# emu.net
KiCad netlist of a schematic drawn in Altium Designer
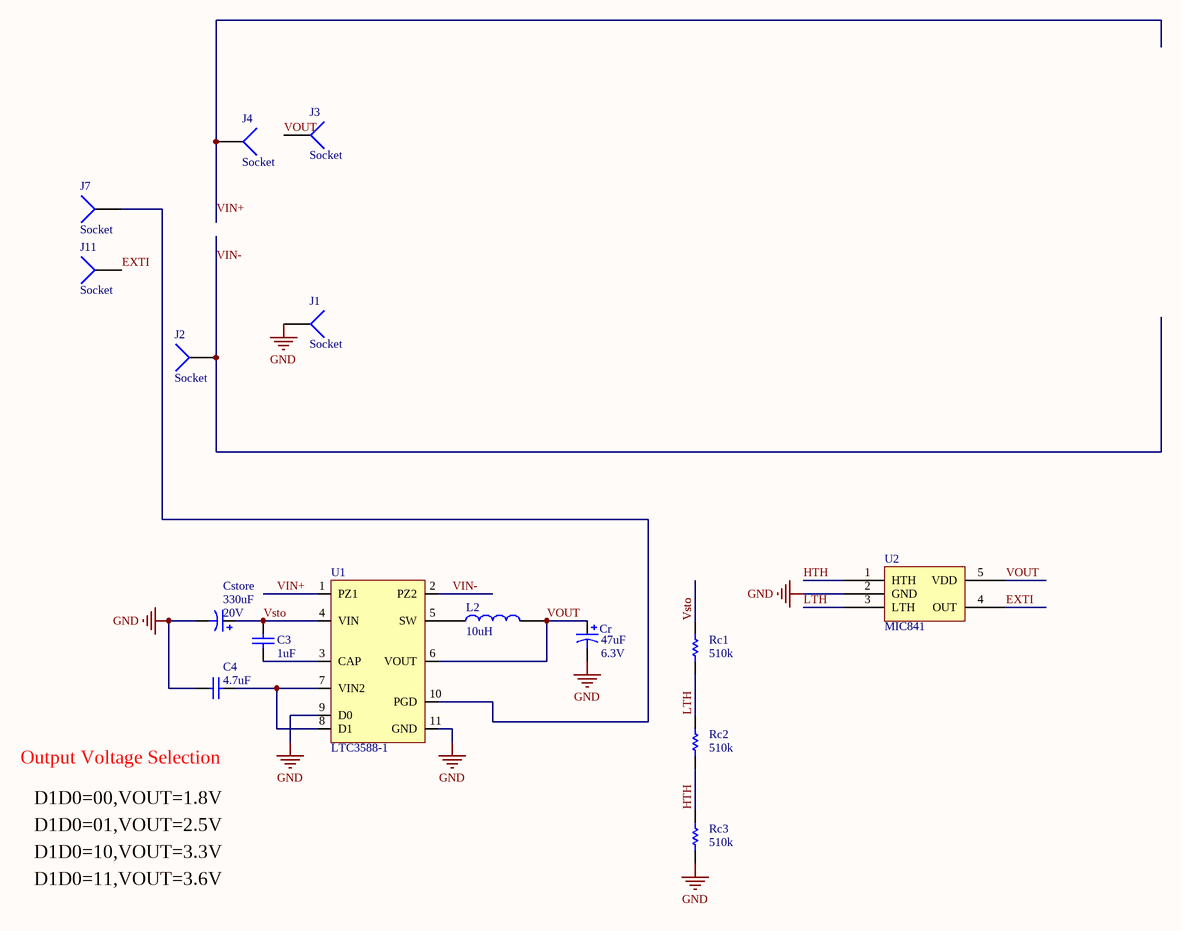
[diagram p0: emu.SchDoc]

(export (version "E")
  (design (tool "Eeschema 10.0.6"))
  (components
    (comp (ref "C3")
      (value "1uF")
      (footprint "6-0805_N")
      (description "Capacitor")
      (fields (field (name "Comment") "CAP") (field (name "PUBLISHER") "Altium Limited"))
      (libsource (lib "Harry_PCBLib") (part "Cap"))
    )
    (comp (ref "C4")
      (value "4.7uF")
      (footprint "6-0805_N")
      (description "Capacitor")
      (fields (field (name "Comment") "CAP") (field (name "PUBLISHER") "Altium Limited"))
      (libsource (lib "Harry_PCBLib") (part "Cap"))
    )
    (comp (ref "Cr")
      (value "6.3V")
      (footprint "3216[1206]")
      (description "Polarized Capacitor (Radial)")
      (fields (field (name "ALTIUM_VALUE") "47uF") (field (name "PUBLISHER") "Altium Limited"))
      (libsource (lib "Miscellaneous Devices") (part "Cap Pol1"))
    )
    (comp (ref "Cstore")
      (value "330uF")
      (footprint "HDR1X2")
      (description "Polarized Capacitor (Radial)")
      (fields
        (field (name "NOMINAL VOLTAGE") "20V")
        (field (name "Comment") "Cap Pol1")
        (field (name "PUBLISHER") "Altium Limited")
      )
      (libsource (lib "Miscellaneous Devices") (part "Cap Pol1"))
    )
    (comp (ref "J1")
      (value "Socket")
      (footprint "PIN1")
      (fields (field (name "PUBLISHER") "Altium Limited"))
      (libsource (lib "Miscellaneous Connectors") (part "Socket"))
    )
    (comp (ref "J2")
      (value "Socket")
      (footprint "PIN1")
      (fields (field (name "PUBLISHER") "Altium Limited"))
      (libsource (lib "Miscellaneous Connectors") (part "Socket"))
    )
    (comp (ref "J3")
      (value "Socket")
      (footprint "PIN1")
      (fields (field (name "PUBLISHER") "Altium Limited"))
      (libsource (lib "Miscellaneous Connectors") (part "Socket"))
    )
    (comp (ref "J4")
      (value "Socket")
      (footprint "PIN1")
      (fields (field (name "PUBLISHER") "Altium Limited"))
      (libsource (lib "Miscellaneous Connectors") (part "Socket"))
    )
    (comp (ref "J7")
      (value "Socket")
      (footprint "PIN1")
      (fields (field (name "PUBLISHER") "Altium Limited"))
      (libsource (lib "Miscellaneous Connectors") (part "Socket"))
    )
    (comp (ref "J11")
      (value "Socket")
      (footprint "PIN1")
      (fields (field (name "PUBLISHER") "Altium Limited"))
      (libsource (lib "Miscellaneous Connectors") (part "Socket"))
    )
    (comp (ref "L2") (value "10uH") (footprint "SMD SS16") (libsource (lib "Harry_PCBLib") (part "INDUCTOR")))
    (comp (ref "Rc1")
      (value "510k")
      (footprint "6-0805_N")
      (description "Resistor")
      (fields (field (name "Comment") "Res1") (field (name "PUBLISHER") "Altium Limited"))
      (libsource (lib "Miscellaneous Devices") (part "Res1"))
    )
    (comp (ref "Rc2")
      (value "510k")
      (footprint "6-0805_N")
      (description "Resistor")
      (fields (field (name "Comment") "Res1") (field (name "PUBLISHER") "Altium Limited"))
      (libsource (lib "Miscellaneous Devices") (part "Res1"))
    )
    (comp (ref "Rc3")
      (value "510k")
      (footprint "6-0805_N")
      (description "Resistor")
      (fields (field (name "Comment") "Res1") (field (name "PUBLISHER") "Altium Limited"))
      (libsource (lib "Miscellaneous Devices") (part "Res1"))
    )
    (comp (ref "U1")
      (value "LTC3588-1")
      (footprint "LTC 3588-1")
      (description "Nanopower energy harvesting power supply")
      (libsource (lib "Self-power SSHI") (part "LTC3588-1"))
    )
    (comp (ref "U2")
      (value "MIC841")
      (footprint "SOT65P210X90-5L20N")
      (libsource (lib "MIC841") (part "Component_1"))
    )
  )
  (nets
    (net (code "1") (name "/EXTI") (class "Default")
      (node (ref "J11") (pin "1") (pinfunction "1_1") (pintype "passive"))
      (node (ref "U2") (pin "4") (pinfunction "OUT_4") (pintype "passive"))
    )
    (net (code "2") (name "/HTH") (class "Default")
      (node (ref "Rc2") (pin "1") (pinfunction "1_1") (pintype "passive"))
      (node (ref "Rc3") (pin "2") (pinfunction "2_2") (pintype "passive"))
      (node (ref "U2") (pin "1") (pinfunction "HTH_1") (pintype "passive"))
    )
    (net (code "3") (name "/LTH") (class "Default")
      (node (ref "Rc1") (pin "1") (pinfunction "1_1") (pintype "passive"))
      (node (ref "Rc2") (pin "2") (pinfunction "2_2") (pintype "passive"))
      (node (ref "U2") (pin "3") (pinfunction "LTH_3") (pintype "passive"))
    )
    (net (code "4") (name "/VIN+") (class "Default")
      (node (ref "J4") (pin "1") (pinfunction "1_1") (pintype "passive"))
      (node (ref "U1") (pin "1") (pinfunction "PZ1_1") (pintype "passive"))
    )
    (net (code "5") (name "/VIN-") (class "Default")
      (node (ref "J2") (pin "1") (pinfunction "1_1") (pintype "passive"))
      (node (ref "U1") (pin "2") (pinfunction "PZ2_2") (pintype "passive"))
    )
    (net (code "6") (name "/VOUT") (class "Default")
      (node (ref "Cr") (pin "1") (pinfunction "1_1") (pintype "passive"))
      (node (ref "J3") (pin "1") (pinfunction "1_1") (pintype "passive"))
      (node (ref "L2") (pin "2") (pinfunction "2_2") (pintype "passive"))
      (node (ref "U1") (pin "6") (pinfunction "VOUT_6") (pintype "passive"))
      (node (ref "U2") (pin "5") (pinfunction "VDD_5") (pintype "passive"))
    )
    (net (code "7") (name "/Vsto") (class "Default")
      (node (ref "C3") (pin "2") (pinfunction "2_2") (pintype "passive"))
      (node (ref "Cstore") (pin "1") (pinfunction "1_1") (pintype "passive"))
      (node (ref "Rc1") (pin "2") (pinfunction "2_2") (pintype "passive"))
      (node (ref "U1") (pin "4") (pinfunction "VIN_4") (pintype "passive"))
    )
    (net (code "8") (name "GND") (class "Default")
      (node (ref "C4") (pin "2") (pinfunction "2_2") (pintype "passive"))
      (node (ref "Cr") (pin "2") (pinfunction "2_2") (pintype "passive"))
      (node (ref "Cstore") (pin "2") (pinfunction "2_2") (pintype "passive"))
      (node (ref "J1") (pin "1") (pinfunction "1_1") (pintype "passive"))
      (node (ref "Rc3") (pin "1") (pinfunction "1_1") (pintype "passive"))
      (node (ref "U1") (pin "11") (pinfunction "GND_11") (pintype "passive"))
      (node (ref "U1") (pin "9") (pinfunction "D0_9") (pintype "passive"))
      (node (ref "U2") (pin "2") (pinfunction "GND_2") (pintype "passive"))
    )
    (net (code "9") (name "Net-(U1-CAP)") (class "Default")
      (node (ref "C3") (pin "1") (pinfunction "1_1") (pintype "passive"))
      (node (ref "U1") (pin "3") (pinfunction "CAP_3") (pintype "passive"))
    )
    (net (code "10") (name "Net-(U1-D1)") (class "Default")
      (node (ref "C4") (pin "1") (pinfunction "1_1") (pintype "passive"))
      (node (ref "U1") (pin "7") (pinfunction "VIN2_7") (pintype "passive"))
      (node (ref "U1") (pin "8") (pinfunction "D1_8") (pintype "passive"))
    )
    (net (code "11") (name "Net-(U1-PGD)") (class "Default")
      (node (ref "J7") (pin "1") (pinfunction "1_1") (pintype "passive"))
      (node (ref "U1") (pin "10") (pinfunction "PGD_10") (pintype "passive"))
    )
    (net (code "12") (name "Net-(U1-SW)") (class "Default")
      (node (ref "L2") (pin "1") (pinfunction "1_1") (pintype "passive"))
      (node (ref "U1") (pin "5") (pinfunction "SW_5") (pintype "passive"))
    )
  )
)
